# ARDUINO.net
KiCad netlist of a schematic drawn in Altium Designer
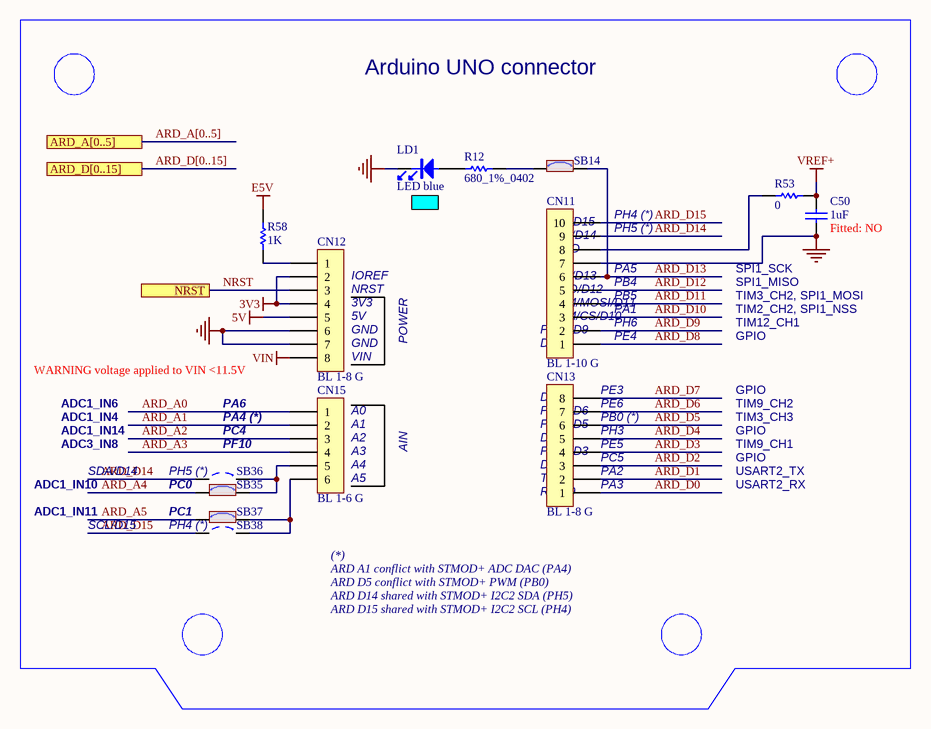
[diagram p0: ARDUINO.SchDoc]

(export (version "E")
  (design (tool "Eeschema 10.0.6"))
  (components
    (comp (ref "C50")
      (value "1uF")
      (footprint "0603C")
      (description "Capacitor,1uF,16V,X5R,10%,0603,YAGEO")
      (fields (field (name "FITTED") "NO"))
      (libsource (lib "MCD_TOOLS_CAPACITOR") (part "Cap_1uF_X5R_10%_0603"))
    )
    (comp (ref "CN11")
      (value "BL 1-10 G")
      (footprint "HDR_1X10_2R54_W")
      (description "Header, 10-Pin, Single row, female, THT, 2.54")
      (libsource (lib "MCD_TOOLS_CONNECTOR") (part "Header 10X1_Female_THT"))
    )
    (comp (ref "CN12")
      (value "BL 1-8 G")
      (footprint "HDR_1X8_2R54_W")
      (description "Header, 8-Pins, Single row, female, THT, 2.54")
      (libsource (lib "") (part "Header 8X1_Female_THT_1"))
    )
    (comp (ref "CN13")
      (value "BL 1-8 G")
      (footprint "HDR_1X8_2R54_W")
      (description "Header, 8-Pins, Single row, female, THT, 2.54")
      (libsource (lib "MCD_TOOLS_CONNECTOR") (part "Header 8X1_Female_THT"))
    )
    (comp (ref "CN15")
      (value "BL 1-6 G")
      (footprint "HDR_1X6_2R54_W")
      (description "Header, 6-Pins, Single row, female THT, 2.54")
      (libsource (lib "MCD_TOOLS_CONNECTOR") (part "Header 6X1_Female_THT"))
    )
    (comp (ref "LD1")
      (value "LED blue")
      (footprint "0603D")
      (description "LED blue 0603")
      (libsource (lib "MCD_TEMP_NPA") (part "LED_blue"))
    )
    (comp (ref "R12")
      (value "680_1%_0402")
      (footprint "0402R")
      (description "Resistor,680,0402,1%,YAGEO")
      (libsource (lib "MCD_TEMP_NPA") (part "Res_680_1%_0402"))
    )
    (comp (ref "R53")
      (value "0")
      (footprint "0402R")
      (description "Resistor,0,0402,5%,YAGEO")
      (libsource (lib "MCD_TOOLS") (part "Res_0_5%_0402"))
    )
    (comp (ref "R58")
      (value "1K")
      (footprint "0402R")
      (description "Resistor,1K,0402,1%,YAGEO")
      (libsource (lib "MCD_TOOLS_RESISTOR") (part "Res_1K_1%_0402"))
    )
    (comp (ref "SB14")
      (value "Solder Bridge ON")
      (footprint "JP2_SMD")
      (libsource (lib "MCD_TOOLS") (part "SB_ON"))
    )
    (comp (ref "SB35")
      (value "Solder Bridge ON")
      (footprint "JP2_SMD")
      (libsource (lib "MCD_TOOLS") (part "SB_ON"))
    )
    (comp (ref "SB36")
      (value "Solder Bridge OFF")
      (footprint "JP2_SMD")
      (libsource (lib "MCD_TOOLS") (part "SB_OFF"))
    )
    (comp (ref "SB37")
      (value "Solder Bridge ON")
      (footprint "JP2_SMD")
      (libsource (lib "MCD_TOOLS") (part "SB_ON"))
    )
    (comp (ref "SB38")
      (value "Solder Bridge OFF")
      (footprint "JP2_SMD")
      (libsource (lib "MCD_TOOLS") (part "SB_OFF"))
    )
  )
  (nets
    (net (code "1") (name "/ARD_A0") (class "Default")
      (node (ref "CN15") (pin "1") (pinfunction "1_1") (pintype "passive"))
    )
    (net (code "2") (name "/ARD_A1") (class "Default")
      (node (ref "CN15") (pin "2") (pinfunction "2_2") (pintype "passive"))
    )
    (net (code "3") (name "/ARD_A2") (class "Default")
      (node (ref "CN15") (pin "3") (pinfunction "3_3") (pintype "passive"))
    )
    (net (code "4") (name "/ARD_A3") (class "Default")
      (node (ref "CN15") (pin "4") (pinfunction "4_4") (pintype "passive"))
    )
    (net (code "5") (name "/ARD_A4") (class "Default")
      (node (ref "SB35") (pin "1") (pinfunction "1_1") (pintype "passive"))
    )
    (net (code "6") (name "/ARD_A5") (class "Default")
      (node (ref "SB37") (pin "1") (pinfunction "1_1") (pintype "passive"))
    )
    (net (code "8") (name "/ARD_D0") (class "Default")
      (node (ref "CN13") (pin "1") (pinfunction "1_1") (pintype "passive"))
    )
    (net (code "9") (name "/ARD_D1") (class "Default")
      (node (ref "CN13") (pin "2") (pinfunction "2_2") (pintype "passive"))
    )
    (net (code "10") (name "/ARD_D2") (class "Default")
      (node (ref "CN13") (pin "3") (pinfunction "3_3") (pintype "passive"))
    )
    (net (code "11") (name "/ARD_D3") (class "Default")
      (node (ref "CN13") (pin "4") (pinfunction "4_4") (pintype "passive"))
    )
    (net (code "12") (name "/ARD_D4") (class "Default")
      (node (ref "CN13") (pin "5") (pinfunction "5_5") (pintype "passive"))
    )
    (net (code "13") (name "/ARD_D5") (class "Default")
      (node (ref "CN13") (pin "6") (pinfunction "6_6") (pintype "passive"))
    )
    (net (code "14") (name "/ARD_D6") (class "Default")
      (node (ref "CN13") (pin "7") (pinfunction "7_7") (pintype "passive"))
    )
    (net (code "15") (name "/ARD_D7") (class "Default")
      (node (ref "CN13") (pin "8") (pinfunction "8_8") (pintype "passive"))
    )
    (net (code "16") (name "/ARD_D8") (class "Default")
      (node (ref "CN11") (pin "1") (pinfunction "1_1") (pintype "passive"))
    )
    (net (code "17") (name "/ARD_D9") (class "Default")
      (node (ref "CN11") (pin "2") (pinfunction "2_2") (pintype "passive"))
    )
    (net (code "18") (name "/ARD_D10") (class "Default")
      (node (ref "CN11") (pin "3") (pinfunction "3_3") (pintype "passive"))
    )
    (net (code "19") (name "/ARD_D11") (class "Default")
      (node (ref "CN11") (pin "4") (pinfunction "4_4") (pintype "passive"))
    )
    (net (code "20") (name "/ARD_D12") (class "Default")
      (node (ref "CN11") (pin "5") (pinfunction "5_5") (pintype "passive"))
    )
    (net (code "21") (name "/ARD_D13") (class "Default")
      (node (ref "CN11") (pin "6") (pinfunction "6_6") (pintype "passive"))
      (node (ref "SB14") (pin "2") (pinfunction "2_2") (pintype "passive"))
    )
    (net (code "22") (name "/ARD_D14") (class "Default")
      (node (ref "CN11") (pin "9") (pinfunction "9_9") (pintype "passive"))
      (node (ref "SB36") (pin "1") (pinfunction "1_1") (pintype "passive"))
    )
    (net (code "23") (name "/ARD_D15") (class "Default")
      (node (ref "CN11") (pin "10") (pinfunction "10_10") (pintype "passive"))
      (node (ref "SB38") (pin "1") (pinfunction "1_1") (pintype "passive"))
    )
    (net (code "25") (name "/NRST") (class "Default")
      (node (ref "CN12") (pin "3") (pinfunction "3_3") (pintype "passive"))
    )
    (net (code "26") (name "3V3") (class "Default")
      (node (ref "CN12") (pin "2") (pinfunction "2_2") (pintype "passive"))
      (node (ref "CN12") (pin "4") (pinfunction "4_4") (pintype "passive"))
    )
    (net (code "27") (name "5V") (class "Default")
      (node (ref "CN12") (pin "5") (pinfunction "5_5") (pintype "passive"))
    )
    (net (code "28") (name "E5V") (class "Default")
      (node (ref "R58") (pin "2") (pinfunction "2_2") (pintype "passive"))
    )
    (net (code "29") (name "GND") (class "Default")
      (node (ref "C50") (pin "1") (pinfunction "1_1") (pintype "passive"))
      (node (ref "CN11") (pin "7") (pinfunction "7_7") (pintype "passive"))
      (node (ref "CN12") (pin "6") (pinfunction "6_6") (pintype "passive"))
      (node (ref "CN12") (pin "7") (pinfunction "7_7") (pintype "passive"))
      (node (ref "LD1") (pin "2") (pintype "passive"))
    )
    (net (code "30") (name "Net-(CN11-Pad8)") (class "Default")
      (node (ref "CN11") (pin "8") (pinfunction "8_8") (pintype "passive"))
      (node (ref "R53") (pin "1") (pinfunction "1_1") (pintype "passive"))
    )
    (net (code "31") (name "Net-(CN12-Pad1)") (class "Default")
      (node (ref "CN12") (pin "1") (pinfunction "1_1") (pintype "passive"))
      (node (ref "R58") (pin "1") (pinfunction "1_1") (pintype "passive"))
    )
    (net (code "32") (name "Net-(CN15-Pad5)") (class "Default")
      (node (ref "CN15") (pin "5") (pinfunction "5_5") (pintype "passive"))
      (node (ref "SB35") (pin "2") (pinfunction "2_2") (pintype "passive"))
      (node (ref "SB36") (pin "2") (pinfunction "2_2") (pintype "passive"))
    )
    (net (code "33") (name "Net-(CN15-Pad6)") (class "Default")
      (node (ref "CN15") (pin "6") (pinfunction "6_6") (pintype "passive"))
      (node (ref "SB37") (pin "2") (pinfunction "2_2") (pintype "passive"))
      (node (ref "SB38") (pin "2") (pinfunction "2_2") (pintype "passive"))
    )
    (net (code "34") (name "Net-(LD1-Pad1)") (class "Default")
      (node (ref "LD1") (pin "1") (pintype "passive"))
      (node (ref "R12") (pin "1") (pinfunction "1_1") (pintype "passive"))
    )
    (net (code "35") (name "Net-(R12-Pad2)") (class "Default")
      (node (ref "R12") (pin "2") (pinfunction "2_2") (pintype "passive"))
      (node (ref "SB14") (pin "1") (pinfunction "1_1") (pintype "passive"))
    )
    (net (code "36") (name "VIN") (class "Default")
      (node (ref "CN12") (pin "8") (pinfunction "8_8") (pintype "passive"))
    )
    (net (code "37") (name "VREF+") (class "Default")
      (node (ref "C50") (pin "2") (pinfunction "2_2") (pintype "passive"))
      (node (ref "R53") (pin "2") (pinfunction "2_2") (pintype "passive"))
    )
  )
)
